# MainBoard_MCU_Power.net
KiCad netlist of a schematic drawn in Altium Designer
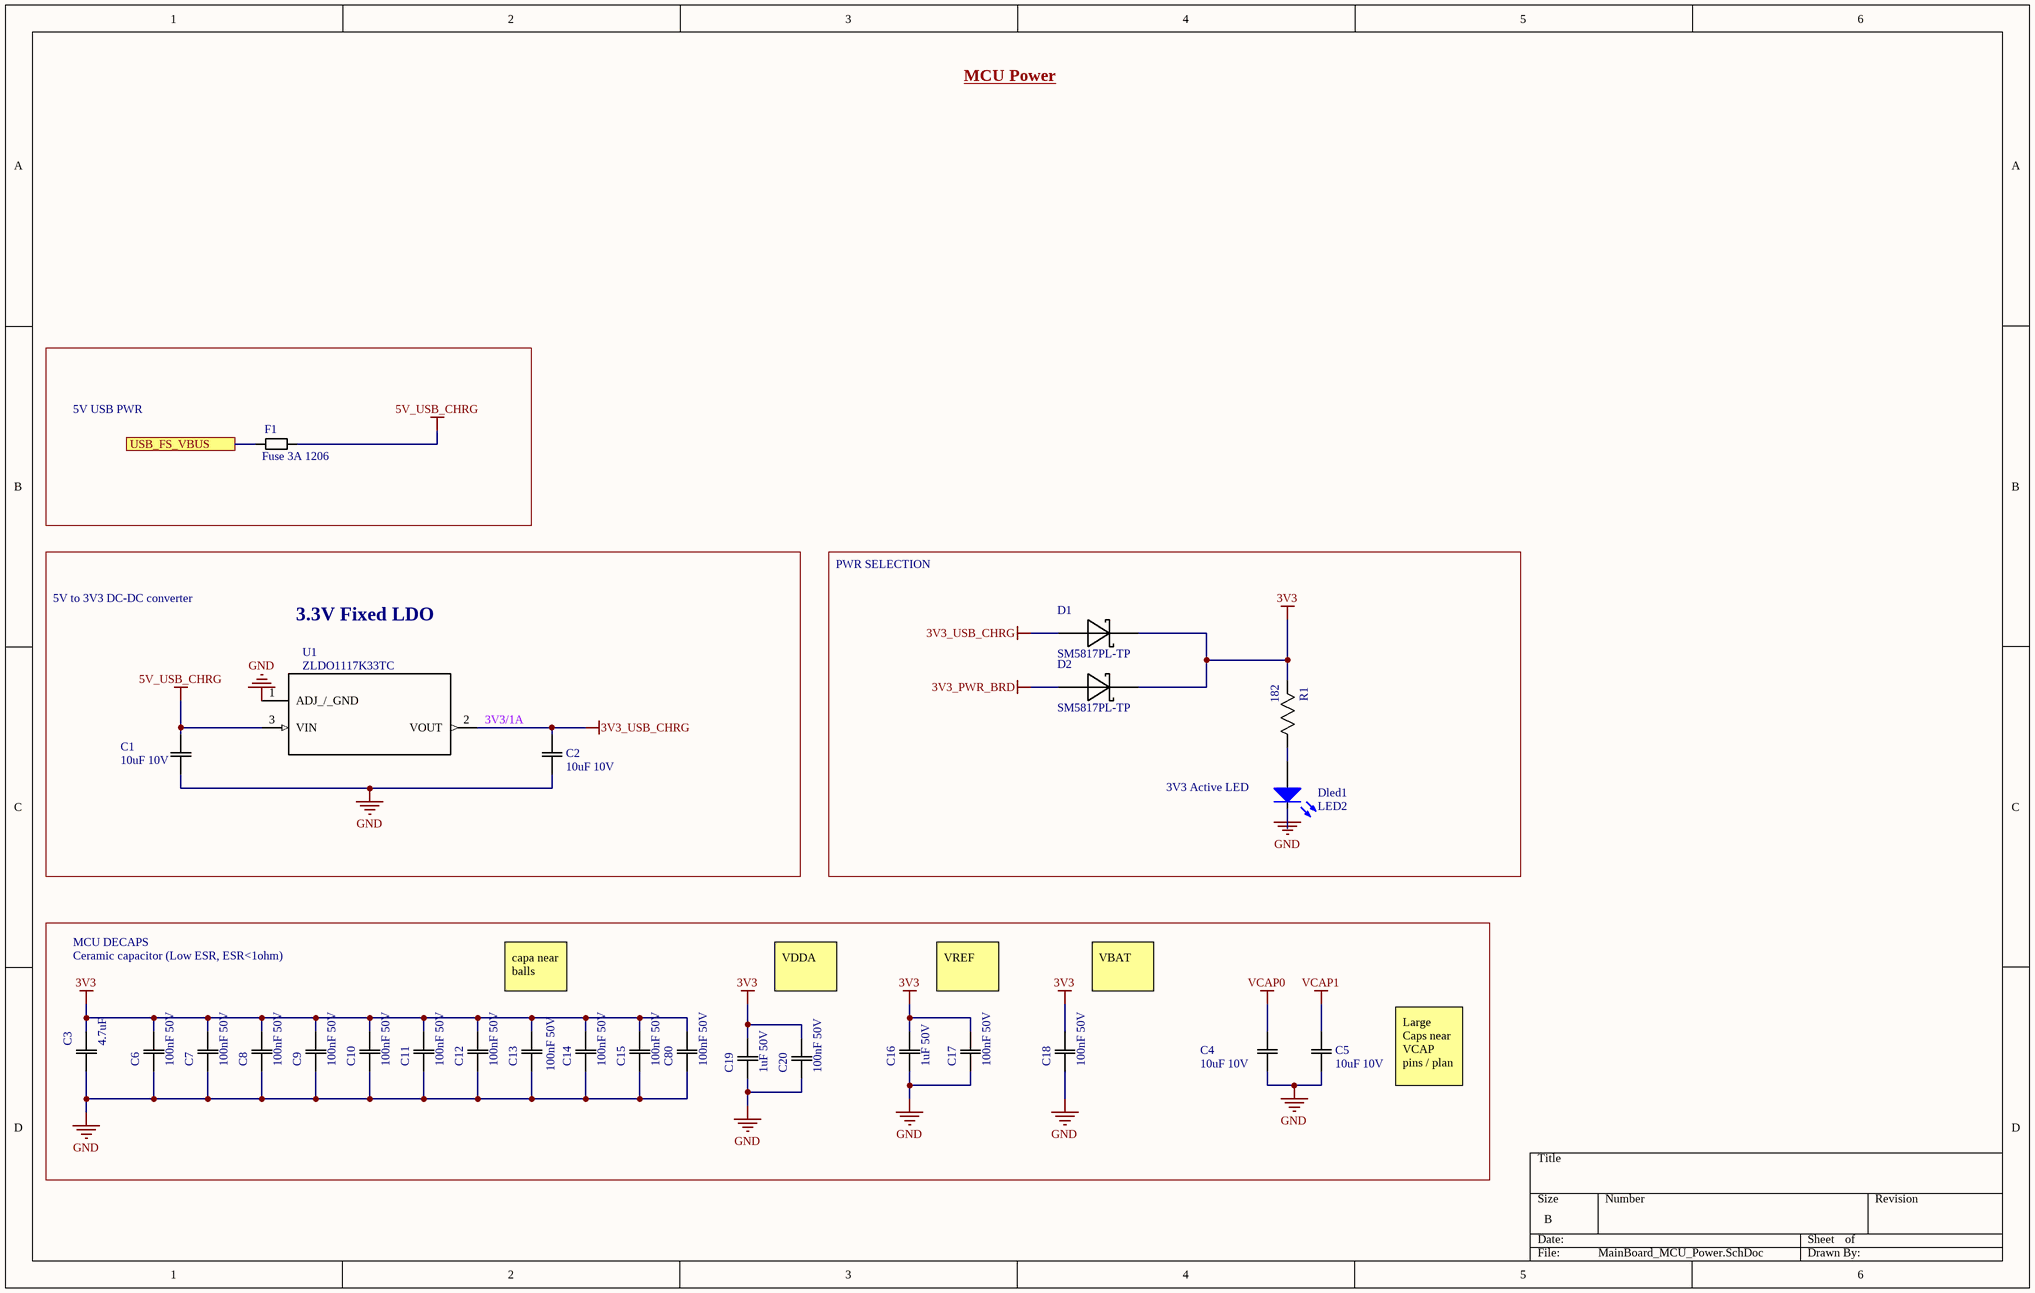
[diagram p0: MainBoard_MCU_Power.SchDoc]

(export (version "E")
  (design (tool "Eeschema 10.0.6"))
  (components
    (comp (ref "C1")
      (value "10uF 10V")
      (footprint "0805")
      (description "CAP CER 10UF 10V X5R 0805")
      (fields (field (name "TOLERANCE") "10%"))
      (libsource (lib "AltiumLibraries") (part "CAP 10uF 10V"))
    )
    (comp (ref "C2")
      (value "10uF 10V")
      (footprint "0805")
      (description "CAP CER 10UF 10V X5R 0805")
      (fields (field (name "TOLERANCE") "10%"))
      (libsource (lib "AltiumLibraries") (part "CAP 10uF 10V"))
    )
    (comp (ref "C3")
      (value "4.7uF")
      (footprint "0805")
      (description "CAP CER 4.7UF 35V X7R 0603/0805")
      (fields (field (name "TOLERANCE") "10%"))
      (libsource (lib "AltiumLibraries") (part "CAP 4.7uF 35V"))
    )
    (comp (ref "C4")
      (value "10uF 10V")
      (footprint "0805")
      (description "CAP CER 10UF 10V X5R 0805")
      (fields (field (name "TOLERANCE") "10%"))
      (libsource (lib "AltiumLibraries") (part "CAP 10uF 10V"))
    )
    (comp (ref "C5")
      (value "10uF 10V")
      (footprint "0805")
      (description "CAP CER 10UF 10V X5R 0805")
      (fields (field (name "TOLERANCE") "10%"))
      (libsource (lib "AltiumLibraries") (part "CAP 10uF 10V"))
    )
    (comp (ref "C6")
      (value "100nF 50V")
      (footprint "0805")
      (description "CAP CER 0.1UF 50V X7R 0805")
      (fields (field (name "TOLERANCE") "10%"))
      (libsource (lib "AltiumLibraries") (part "CAP 100nF 50V"))
    )
    (comp (ref "C7")
      (value "100nF 50V")
      (footprint "0805")
      (description "CAP CER 0.1UF 50V X7R 0805")
      (fields (field (name "TOLERANCE") "10%"))
      (libsource (lib "AltiumLibraries") (part "CAP 100nF 50V"))
    )
    (comp (ref "C8")
      (value "100nF 50V")
      (footprint "0805")
      (description "CAP CER 0.1UF 50V X7R 0805")
      (fields (field (name "TOLERANCE") "10%"))
      (libsource (lib "AltiumLibraries") (part "CAP 100nF 50V"))
    )
    (comp (ref "C9")
      (value "100nF 50V")
      (footprint "0805")
      (description "CAP CER 0.1UF 50V X7R 0805")
      (fields (field (name "TOLERANCE") "10%"))
      (libsource (lib "AltiumLibraries") (part "CAP 100nF 50V"))
    )
    (comp (ref "C10")
      (value "100nF 50V")
      (footprint "0805")
      (description "CAP CER 0.1UF 50V X7R 0805")
      (fields (field (name "TOLERANCE") "10%"))
      (libsource (lib "AltiumLibraries") (part "CAP 100nF 50V"))
    )
    (comp (ref "C11")
      (value "100nF 50V")
      (footprint "0805")
      (description "CAP CER 0.1UF 50V X7R 0805")
      (fields (field (name "TOLERANCE") "10%"))
      (libsource (lib "AltiumLibraries") (part "CAP 100nF 50V"))
    )
    (comp (ref "C12")
      (value "100nF 50V")
      (footprint "0805")
      (description "CAP CER 0.1UF 50V X7R 0805")
      (fields (field (name "TOLERANCE") "10%"))
      (libsource (lib "AltiumLibraries") (part "CAP 100nF 50V"))
    )
    (comp (ref "C13")
      (value "100nF 50V")
      (footprint "0805")
      (description "CAP CER 0.1UF 50V X7R 0805")
      (fields (field (name "TOLERANCE") "10%"))
      (libsource (lib "AltiumLibraries") (part "CAP 100nF 50V"))
    )
    (comp (ref "C14")
      (value "100nF 50V")
      (footprint "0805")
      (description "CAP CER 0.1UF 50V X7R 0805")
      (fields (field (name "TOLERANCE") "10%"))
      (libsource (lib "AltiumLibraries") (part "CAP 100nF 50V"))
    )
    (comp (ref "C15")
      (value "100nF 50V")
      (footprint "0805")
      (description "CAP CER 0.1UF 50V X7R 0805")
      (fields (field (name "TOLERANCE") "10%"))
      (libsource (lib "AltiumLibraries") (part "CAP 100nF 50V"))
    )
    (comp (ref "C16")
      (value "1uF 50V")
      (footprint "0805")
      (description "CAP CER 1UF 50V X7R 0805")
      (fields (field (name "TOLERANCE") "10%"))
      (libsource (lib "AltiumLibraries") (part "CAP 1uF 50V"))
    )
    (comp (ref "C17")
      (value "100nF 50V")
      (footprint "0805")
      (description "CAP CER 0.1UF 50V X7R 0805")
      (fields (field (name "TOLERANCE") "10%"))
      (libsource (lib "AltiumLibraries") (part "CAP 100nF 50V"))
    )
    (comp (ref "C18")
      (value "100nF 50V")
      (footprint "0805")
      (description "CAP CER 0.1UF 50V X7R 0805")
      (fields (field (name "TOLERANCE") "10%"))
      (libsource (lib "AltiumLibraries") (part "CAP 100nF 50V"))
    )
    (comp (ref "C19")
      (value "1uF 50V")
      (footprint "0805")
      (description "CAP CER 1UF 50V X7R 0805")
      (fields (field (name "TOLERANCE") "10%"))
      (libsource (lib "AltiumLibraries") (part "CAP 1uF 50V"))
    )
    (comp (ref "C20")
      (value "100nF 50V")
      (footprint "0805")
      (description "CAP CER 0.1UF 50V X7R 0805")
      (fields (field (name "TOLERANCE") "10%"))
      (libsource (lib "AltiumLibraries") (part "CAP 100nF 50V"))
    )
    (comp (ref "C80")
      (value "100nF 50V")
      (footprint "0805")
      (description "CAP CER 0.1UF 50V X7R 0805")
      (fields (field (name "TOLERANCE") "10%"))
      (libsource (lib "AltiumLibraries") (part "CAP 100nF 50V"))
    )
    (comp (ref "D1")
      (value "SM5817PL-TP")
      (footprint "SOD-123")
      (description "Diode Schottky 20V 1A Surface Mount SOD-123FL")
      (fields (field (name "MF") "Micro Commercial Co"))
      (libsource (lib "AltiumLibraries") (part "DIODE SCHOTTKY 20V 1A"))
    )
    (comp (ref "D2")
      (value "SM5817PL-TP")
      (footprint "SOD-123")
      (description "Diode Schottky 20V 1A Surface Mount SOD-123FL")
      (fields (field (name "MF") "Micro Commercial Co"))
      (libsource (lib "AltiumLibraries") (part "DIODE SCHOTTKY 20V 1A"))
    )
    (comp (ref "Dled1")
      (value "LED2")
      (footprint "3.2X1.6X1.1")
      (description "Typical RED, GREEN, YELLOW, AMBER GaAs LED")
      (libsource (lib "AltiumLibraries") (part "LED GREEN SMD"))
    )
    (comp (ref "F1")
      (value "Fuse 3A 1206")
      (footprint "1206")
      (description "FUSE 3A 63V AC/DC SLOW 1206")
      (libsource (lib "AltiumLibraries") (part "FUSE 3A 63V SLOW"))
    )
    (comp (ref "R1")
      (value "182")
      (footprint "0805")
      (description "RES SMD 182 OHM 1% 1/8W 0805")
      (fields (field (name "TOLERANCE") "1%"))
      (libsource (lib "AltiumLibraries") (part "RES 182.0 1/8W"))
    )
    (comp (ref "U1")
      (value "ZLDO1117K33TC")
      (footprint "DPAK (TO-252)")
      (description "Linear Voltage Regulator IC Positive Fixed 1 Output  1A TO-252-3")
      (fields (field (name "MF") "Diodes Incorporated"))
      (libsource (lib "AltiumLibraries") (part "ZLDO1117K33TC"))
    )
  )
  (nets
    (net (code "1") (name "/USB_FS_VBUS") (class "Default")
      (node (ref "F1") (pin "1") (pinfunction "1_1") (pintype "passive"))
    )
    (net (code "2") (name "3V3") (class "Default")
      (node (ref "C10") (pin "2") (pinfunction "C2_2") (pintype "passive"))
      (node (ref "C11") (pin "2") (pinfunction "C2_2") (pintype "passive"))
      (node (ref "C12") (pin "2") (pinfunction "C2_2") (pintype "passive"))
      (node (ref "C13") (pin "2") (pinfunction "C2_2") (pintype "passive"))
      (node (ref "C14") (pin "2") (pinfunction "C2_2") (pintype "passive"))
      (node (ref "C15") (pin "2") (pinfunction "C2_2") (pintype "passive"))
      (node (ref "C16") (pin "2") (pinfunction "C2_2") (pintype "passive"))
      (node (ref "C17") (pin "2") (pinfunction "C2_2") (pintype "passive"))
      (node (ref "C18") (pin "2") (pinfunction "C2_2") (pintype "passive"))
      (node (ref "C19") (pin "2") (pinfunction "C2_2") (pintype "passive"))
      (node (ref "C20") (pin "2") (pinfunction "C2_2") (pintype "passive"))
      (node (ref "C3") (pin "2") (pinfunction "C2_2") (pintype "passive"))
      (node (ref "C6") (pin "2") (pinfunction "C2_2") (pintype "passive"))
      (node (ref "C7") (pin "2") (pinfunction "C2_2") (pintype "passive"))
      (node (ref "C8") (pin "2") (pinfunction "C2_2") (pintype "passive"))
      (node (ref "C80") (pin "2") (pinfunction "C2_2") (pintype "passive"))
      (node (ref "C9") (pin "2") (pinfunction "C2_2") (pintype "passive"))
      (node (ref "D1") (pin "C") (pinfunction "K_C") (pintype "passive"))
      (node (ref "D2") (pin "C") (pinfunction "K_C") (pintype "passive"))
      (node (ref "R1") (pin "2") (pinfunction "R2_2") (pintype "passive"))
    )
    (net (code "3") (name "3V3_PWR_BRD") (class "Default")
      (node (ref "D2") (pin "A") (pinfunction "A_A") (pintype "passive"))
    )
    (net (code "4") (name "3V3_USB_CHRG") (class "Default")
      (node (ref "C2") (pin "1") (pinfunction "C1_1") (pintype "passive"))
      (node (ref "D1") (pin "A") (pinfunction "A_A") (pintype "passive"))
      (node (ref "U1") (pin "2") (pinfunction "VOUT_2") (pintype "output"))
    )
    (net (code "5") (name "5V_USB_CHRG") (class "Default")
      (node (ref "C1") (pin "1") (pinfunction "C1_1") (pintype "passive"))
      (node (ref "F1") (pin "2") (pinfunction "2_2") (pintype "passive"))
      (node (ref "U1") (pin "3") (pinfunction "VIN_3") (pintype "input"))
    )
    (net (code "6") (name "GND") (class "Default")
      (node (ref "C1") (pin "2") (pinfunction "C2_2") (pintype "passive"))
      (node (ref "C10") (pin "1") (pinfunction "C1_1") (pintype "passive"))
      (node (ref "C11") (pin "1") (pinfunction "C1_1") (pintype "passive"))
      (node (ref "C12") (pin "1") (pinfunction "C1_1") (pintype "passive"))
      (node (ref "C13") (pin "1") (pinfunction "C1_1") (pintype "passive"))
      (node (ref "C14") (pin "1") (pinfunction "C1_1") (pintype "passive"))
      (node (ref "C15") (pin "1") (pinfunction "C1_1") (pintype "passive"))
      (node (ref "C16") (pin "1") (pinfunction "C1_1") (pintype "passive"))
      (node (ref "C17") (pin "1") (pinfunction "C1_1") (pintype "passive"))
      (node (ref "C18") (pin "1") (pinfunction "C1_1") (pintype "passive"))
      (node (ref "C19") (pin "1") (pinfunction "C1_1") (pintype "passive"))
      (node (ref "C2") (pin "2") (pinfunction "C2_2") (pintype "passive"))
      (node (ref "C20") (pin "1") (pinfunction "C1_1") (pintype "passive"))
      (node (ref "C3") (pin "1") (pinfunction "C1_1") (pintype "passive"))
      (node (ref "C4") (pin "2") (pinfunction "C2_2") (pintype "passive"))
      (node (ref "C5") (pin "2") (pinfunction "C2_2") (pintype "passive"))
      (node (ref "C6") (pin "1") (pinfunction "C1_1") (pintype "passive"))
      (node (ref "C7") (pin "1") (pinfunction "C1_1") (pintype "passive"))
      (node (ref "C8") (pin "1") (pinfunction "C1_1") (pintype "passive"))
      (node (ref "C80") (pin "1") (pinfunction "C1_1") (pintype "passive"))
      (node (ref "C9") (pin "1") (pinfunction "C1_1") (pintype "passive"))
      (node (ref "Dled1") (pin "2") (pinfunction "K_2") (pintype "passive"))
      (node (ref "U1") (pin "1") (pinfunction "ADJ_/_GND_1") (pintype "power_in"))
    )
    (net (code "7") (name "Net-(Dled1-A)") (class "Default")
      (node (ref "Dled1") (pin "1") (pinfunction "A_1") (pintype "passive"))
      (node (ref "R1") (pin "1") (pinfunction "R1_1") (pintype "passive"))
    )
    (net (code "8") (name "VCAP0") (class "Default")
      (node (ref "C4") (pin "1") (pinfunction "C1_1") (pintype "passive"))
    )
    (net (code "9") (name "VCAP1") (class "Default")
      (node (ref "C5") (pin "1") (pinfunction "C1_1") (pintype "passive"))
    )
  )
)
